# atmega_can.net
KiCad netlist of a schematic drawn in Altium Designer
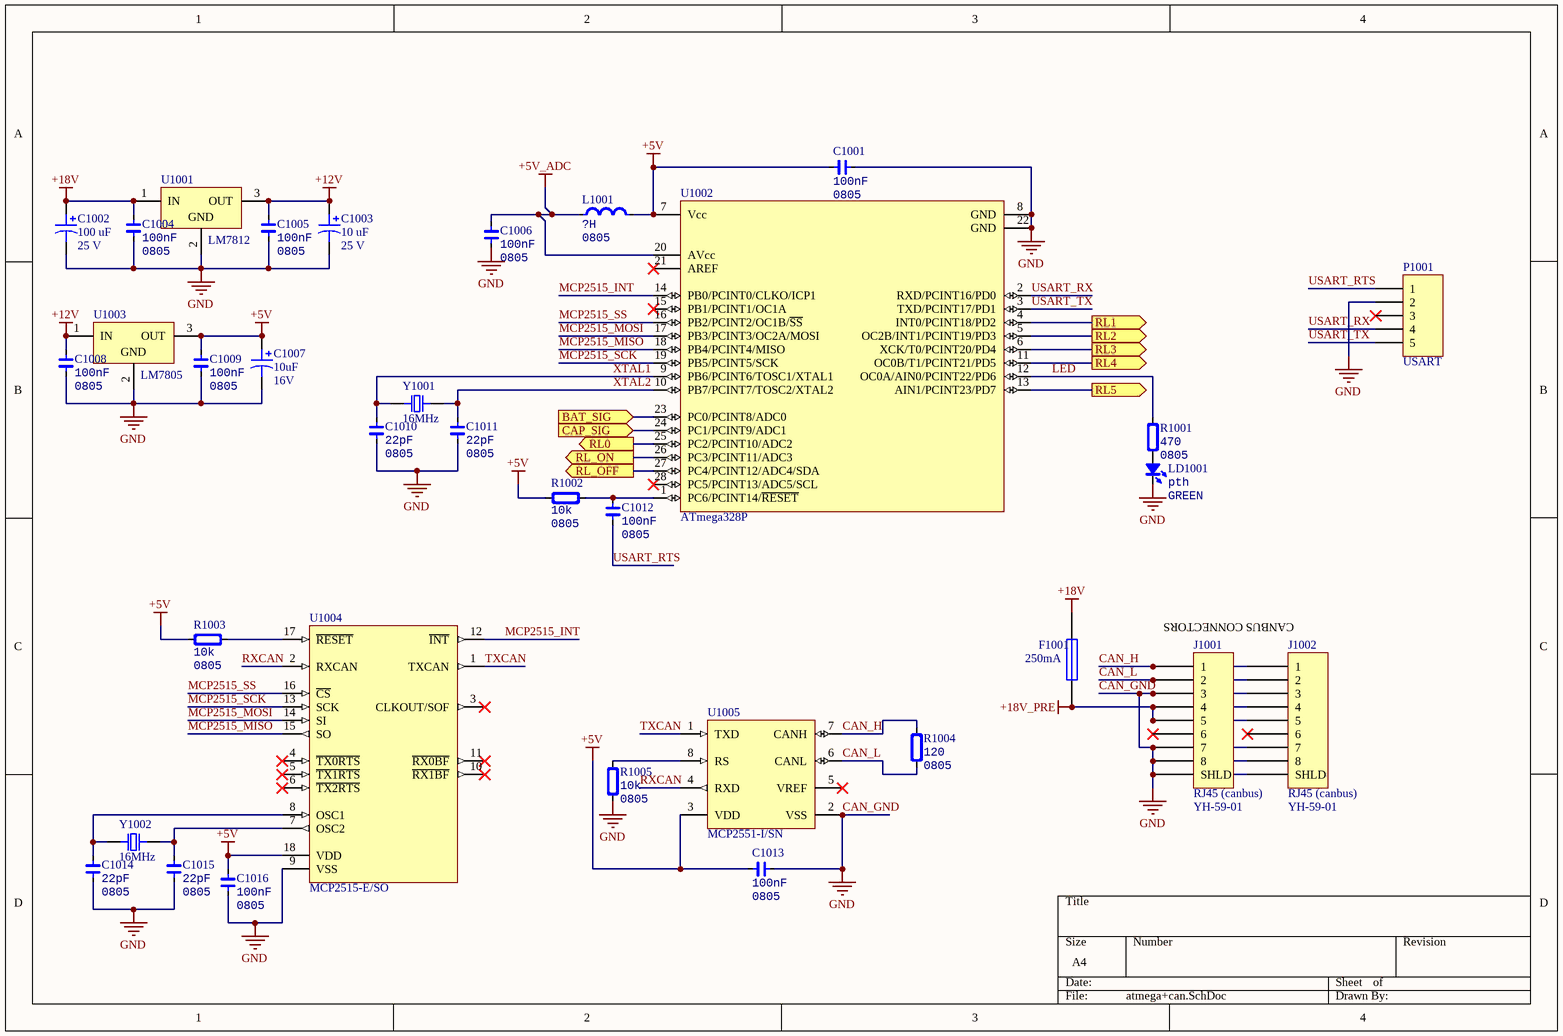
[diagram p0: atmega+can.SchDoc]

(export (version "E")
  (design (tool "Eeschema 10.0.6"))
  (components
    (comp (ref "C1001")
      (value "100nF")
      (footprint "0805C")
      (description "Capacitor")
      (fields (field (name "TYPE") "0805"))
      (libsource (lib "") (part "Cap_0805_1"))
    )
    (comp (ref "C1002")
      (value "100 uF")
      (footprint "CP3.5mm-8.0mm")
      (description "Solid Aluminum Capacitor with Organic Semiconductor Electrolyte: 100uF, 10V, Bulk Pack")
      (fields (field (name "VOLTAGE") "25 V") (field (name "Comment") "CapacitorPol"))
      (libsource (lib "R2R - Nova") (part "CapacitorPol"))
    )
    (comp (ref "C1003")
      (value "10 uF")
      (footprint "CP3.5mm-8.0mm")
      (description "Solid Aluminum Capacitor with Organic Semiconductor Electrolyte: 100uF, 10V, Bulk Pack")
      (fields (field (name "VOLTAGE") "25 V") (field (name "Comment") "CapacitorPol"))
      (libsource (lib "R2R - Nova") (part "CapacitorPol"))
    )
    (comp (ref "C1004")
      (value "100nF")
      (footprint "0805C")
      (description "Capacitor")
      (fields (field (name "TYPE") "0805"))
      (libsource (lib "SCH_Passive") (part "Cap_0805"))
    )
    (comp (ref "C1005")
      (value "100nF")
      (footprint "0805C")
      (description "Capacitor")
      (fields (field (name "TYPE") "0805"))
      (libsource (lib "SCH_Passive") (part "Cap_0805"))
    )
    (comp (ref "C1006")
      (value "100nF")
      (footprint "0805C")
      (description "Capacitor")
      (fields (field (name "TYPE") "0805"))
      (libsource (lib "SCH_Passive") (part "Cap_0805"))
    )
    (comp (ref "C1007")
      (value "10uF")
      (footprint "CP3.5mm-8.0mm")
      (description "Solid Aluminum Capacitor with Organic Semiconductor Electrolyte: 100uF, 10V, Bulk Pack")
      (fields (field (name "VOLTAGE") "16V") (field (name "Comment") "CapacitorPol"))
      (libsource (lib "R2R - Nova") (part "CapacitorPol"))
    )
    (comp (ref "C1008")
      (value "100nF")
      (footprint "0805C")
      (description "Capacitor")
      (fields (field (name "TYPE") "0805"))
      (libsource (lib "SCH_Passive") (part "Cap_0805"))
    )
    (comp (ref "C1009")
      (value "100nF")
      (footprint "0805C")
      (description "Capacitor")
      (fields (field (name "TYPE") "0805"))
      (libsource (lib "SCH_Passive") (part "Cap_0805"))
    )
    (comp (ref "C1010")
      (value "22pF")
      (footprint "0805C")
      (description "Capacitor")
      (fields (field (name "TYPE") "0805"))
      (libsource (lib "SCH_Passive") (part "Cap_0805"))
    )
    (comp (ref "C1011")
      (value "22pF")
      (footprint "0805C")
      (description "Capacitor")
      (fields (field (name "TYPE") "0805"))
      (libsource (lib "SCH_Passive") (part "Cap_0805"))
    )
    (comp (ref "C1012")
      (value "100nF")
      (footprint "0805C")
      (description "Capacitor")
      (fields (field (name "TYPE") "0805"))
      (libsource (lib "") (part "Cap_0805_2"))
    )
    (comp (ref "C1013")
      (value "100nF")
      (footprint "0805C")
      (description "Capacitor")
      (fields (field (name "TYPE") "0805"))
      (libsource (lib "") (part "Cap_0805_1"))
    )
    (comp (ref "C1014")
      (value "22pF")
      (footprint "0805C")
      (description "Capacitor")
      (fields (field (name "TYPE") "0805"))
      (libsource (lib "SCH_Passive") (part "Cap_0805"))
    )
    (comp (ref "C1015")
      (value "22pF")
      (footprint "0805C")
      (description "Capacitor")
      (fields (field (name "TYPE") "0805"))
      (libsource (lib "SCH_Passive") (part "Cap_0805"))
    )
    (comp (ref "C1016")
      (value "100nF")
      (footprint "0805C")
      (description "Capacitor")
      (fields (field (name "TYPE") "0805"))
      (libsource (lib "") (part "Cap_0805_2"))
    )
    (comp (ref "F1001")
      (value "250mA")
      (footprint "Porta Fusivel")
      (description "Fuse")
      (libsource (lib "Miscellaneous Devices") (part "Fuse 1"))
    )
    (comp (ref "J1001")
      (value "RJ45 (canbus)")
      (footprint "ASSMANN A-2004-2-4-LP/FS")
      (description "YH-59-01")
      (fields (field (name "ALTIUM_VALUE") "YH-59-01"))
      (libsource (lib "Connectors") (part "Modular Jack with Shield"))
    )
    (comp (ref "J1002")
      (value "RJ45 (canbus)")
      (footprint "ASSMANN A-2004-2-4-LP/FS")
      (description "YH-59-01")
      (fields (field (name "ALTIUM_VALUE") "YH-59-01"))
      (libsource (lib "Connectors") (part "Modular Jack with Shield"))
    )
    (comp (ref "L1001")
      (value "?H")
      (footprint "0805I")
      (description "Inductor")
      (fields (field (name "TYPE") "0805"))
      (libsource (lib "SCH_Passive") (part "Ind_0805"))
    )
    (comp (ref "LD1001")
      (value "GREEN")
      (footprint "LED3MM")
      (description "LED")
      (fields (field (name "TYPE") "pth"))
      (libsource (lib "SCH_Active") (part "LED_0805"))
    )
    (comp (ref "P1001")
      (value "USART")
      (footprint "HDR1X5")
      (description "Header, 5-Pin")
      (libsource (lib "R2R - Nova") (part "Header 5"))
    )
    (comp (ref "R1001")
      (value "470")
      (footprint "0805C")
      (description "Resistor")
      (fields (field (name "TYPE") "0805"))
      (libsource (lib "SCH_Passive") (part "Res_0805"))
    )
    (comp (ref "R1002")
      (value "10k")
      (footprint "0805C")
      (description "Resistor")
      (fields (field (name "TYPE") "0805"))
      (libsource (lib "SCH_Passive") (part "Res_0805"))
    )
    (comp (ref "R1003")
      (value "10k")
      (footprint "0805C")
      (description "Resistor")
      (fields (field (name "TYPE") "0805"))
      (libsource (lib "SCH_Passive") (part "Res_0805"))
    )
    (comp (ref "R1004")
      (value "120")
      (footprint "0805C")
      (description "Resistor")
      (fields (field (name "TYPE") "0805"))
      (libsource (lib "SCH_Passive") (part "Res_0805"))
    )
    (comp (ref "R1005")
      (value "10k")
      (footprint "0805C")
      (description "Resistor")
      (fields (field (name "TYPE") "0805"))
      (libsource (lib "SCH_Passive") (part "Res_0805"))
    )
    (comp (ref "U1001")
      (value "LM7812")
      (footprint "TO220_deitado")
      (description "Positive-Voltage Regulator")
      (libsource (lib "TI Power Mgt Voltage Regulator") (part "µA7805CKC"))
    )
    (comp (ref "U1002")
      (value "ATmega328P")
      (footprint "DIP28-300(100)")
      (libsource (lib "R2R - Nova") (part "ATmega328P"))
    )
    (comp (ref "U1003")
      (value "LM7805")
      (footprint "TO220_deitado")
      (description "Positive-Voltage Regulator")
      (libsource (lib "TI Power Mgt Voltage Regulator") (part "µA7805CKC"))
    )
    (comp (ref "U1004")
      (value "MCP2515-E/SO")
      (footprint "WSO18_L")
      (description "Stand-Alone CAN Controller With SPI Interface, 18-Pin SOIC, Extended Temperature")
      (libsource (lib "Altium Content Vault") (part "COM-CAN-MCP2515-18"))
    )
    (comp (ref "U1005")
      (value "MCP2551-I/SN")
      (footprint "SOIC08-150(50)")
      (libsource (lib "Altium Content Vault") (part "MCHP-MCP2551-SN8"))
    )
    (comp (ref "Y1001")
      (value "16MHz")
      (footprint "HC49-US-THT")
      (description "Crystal")
      (libsource (lib "R2R - Nova") (part "Crystal"))
    )
    (comp (ref "Y1002")
      (value "16MHz")
      (footprint "HC49-US-THT")
      (description "Crystal")
      (libsource (lib "R2R - Nova") (part "Crystal"))
    )
  )
  (nets
    (net (code "1") (name "+5V") (class "Default")
      (node (ref "C1001") (pin "1") (pinfunction "1_1") (pintype "passive"))
      (node (ref "C1007") (pin "1") (pinfunction "1_1") (pintype "passive"))
      (node (ref "C1009") (pin "2") (pinfunction "2_2") (pintype "passive"))
      (node (ref "C1013") (pin "1") (pinfunction "1_1") (pintype "passive"))
      (node (ref "C1016") (pin "1") (pinfunction "1_1") (pintype "passive"))
      (node (ref "L1001") (pin "2") (pinfunction "2_2") (pintype "passive"))
      (node (ref "R1002") (pin "1") (pinfunction "1_1") (pintype "passive"))
      (node (ref "R1003") (pin "1") (pinfunction "1_1") (pintype "passive"))
      (node (ref "U1002") (pin "7") (pinfunction "Vcc_7") (pintype "passive"))
      (node (ref "U1003") (pin "3") (pinfunction "OUT_3") (pintype "power_in"))
      (node (ref "U1004") (pin "18") (pinfunction "VDD_18") (pintype "power_in"))
      (node (ref "U1005") (pin "3") (pinfunction "VDD_3") (pintype "power_in"))
    )
    (net (code "2") (name "+5V_ADC") (class "Default")
      (node (ref "C1006") (pin "2") (pinfunction "2_2") (pintype "passive"))
      (node (ref "L1001") (pin "1") (pinfunction "1_1") (pintype "passive"))
      (node (ref "U1002") (pin "20") (pinfunction "AVcc_20") (pintype "passive"))
    )
    (net (code "3") (name "+12V") (class "Default")
      (node (ref "C1003") (pin "1") (pinfunction "1_1") (pintype "passive"))
      (node (ref "C1005") (pin "2") (pinfunction "2_2") (pintype "passive"))
      (node (ref "C1008") (pin "2") (pinfunction "2_2") (pintype "passive"))
      (node (ref "U1001") (pin "3") (pinfunction "OUT_3") (pintype "power_in"))
      (node (ref "U1003") (pin "1") (pinfunction "IN_1") (pintype "power_in"))
    )
    (net (code "4") (name "+18V") (class "Default")
      (node (ref "C1002") (pin "1") (pinfunction "1_1") (pintype "passive"))
      (node (ref "C1004") (pin "2") (pinfunction "2_2") (pintype "passive"))
      (node (ref "F1001") (pin "1") (pinfunction "1_1") (pintype "passive"))
      (node (ref "U1001") (pin "1") (pinfunction "IN_1") (pintype "power_in"))
    )
    (net (code "5") (name "+18V_PRE") (class "Default")
      (node (ref "F1001") (pin "2") (pinfunction "2_2") (pintype "passive"))
      (node (ref "J1001") (pin "4") (pinfunction "4_4") (pintype "passive"))
      (node (ref "J1001") (pin "5") (pinfunction "5_5") (pintype "passive"))
      (node (ref "J1002") (pin "4") (pinfunction "4_4") (pintype "passive"))
      (node (ref "J1002") (pin "5") (pinfunction "5_5") (pintype "passive"))
    )
    (net (code "6") (name "/BAT_SIG") (class "Default")
      (node (ref "U1002") (pin "23") (pinfunction "PC0/PCINT8/ADC0_23") (pintype "bidirectional"))
    )
    (net (code "7") (name "/CAN_H") (class "Default")
      (node (ref "J1001") (pin "1") (pinfunction "1_1") (pintype "passive"))
      (node (ref "J1002") (pin "1") (pinfunction "1_1") (pintype "passive"))
      (node (ref "R1004") (pin "2") (pinfunction "2_2") (pintype "passive"))
      (node (ref "U1005") (pin "7") (pinfunction "CANH_7") (pintype "bidirectional"))
    )
    (net (code "8") (name "/CAN_L") (class "Default")
      (node (ref "J1001") (pin "2") (pinfunction "2_2") (pintype "passive"))
      (node (ref "J1002") (pin "2") (pinfunction "2_2") (pintype "passive"))
      (node (ref "R1004") (pin "1") (pinfunction "1_1") (pintype "passive"))
      (node (ref "U1005") (pin "6") (pinfunction "CANL_6") (pintype "bidirectional"))
    )
    (net (code "9") (name "/CAP_SIG") (class "Default")
      (node (ref "U1002") (pin "24") (pinfunction "PC1/PCINT9/ADC1_24") (pintype "bidirectional"))
    )
    (net (code "10") (name "/LED") (class "Default")
      (node (ref "R1001") (pin "2") (pinfunction "2_2") (pintype "passive"))
      (node (ref "U1002") (pin "12") (pinfunction "OC0A/AIN0/PCINT22/PD6_12") (pintype "bidirectional"))
    )
    (net (code "11") (name "/MCP2515_INT") (class "Default")
      (node (ref "U1002") (pin "14") (pinfunction "PB0/PCINT0/CLKO/ICP1_14") (pintype "bidirectional"))
      (node (ref "U1004") (pin "12") (pinfunction "~{INT}_12") (pintype "output"))
    )
    (net (code "12") (name "/MCP2515_MISO") (class "Default")
      (node (ref "U1002") (pin "18") (pinfunction "PB4/PCINT4/MISO_18") (pintype "bidirectional"))
      (node (ref "U1004") (pin "15") (pinfunction "SO_15") (pintype "output"))
    )
    (net (code "13") (name "/MCP2515_MOSI") (class "Default")
      (node (ref "U1002") (pin "17") (pinfunction "PB3/PCINT3/OC2A/MOSI_17") (pintype "bidirectional"))
      (node (ref "U1004") (pin "14") (pinfunction "SI_14") (pintype "input"))
    )
    (net (code "14") (name "/MCP2515_SCK") (class "Default")
      (node (ref "U1002") (pin "19") (pinfunction "PB5/PCINT5/SCK_19") (pintype "bidirectional"))
      (node (ref "U1004") (pin "13") (pinfunction "SCK_13") (pintype "input"))
    )
    (net (code "15") (name "/MCP2515_SS") (class "Default")
      (node (ref "U1002") (pin "16") (pinfunction "PB2/PCINT2/OC1B/~{SS}_16") (pintype "bidirectional"))
      (node (ref "U1004") (pin "16") (pinfunction "~{CS}_16") (pintype "input"))
    )
    (net (code "16") (name "/RL0") (class "Default")
      (node (ref "U1002") (pin "25") (pinfunction "PC2/PCINT10/ADC2_25") (pintype "bidirectional"))
    )
    (net (code "17") (name "/RL1") (class "Default")
      (node (ref "U1002") (pin "4") (pinfunction "INT0/PCINT18/PD2_4") (pintype "bidirectional"))
    )
    (net (code "18") (name "/RL2") (class "Default")
      (node (ref "U1002") (pin "5") (pinfunction "OC2B/INT1/PCINT19/PD3_5") (pintype "bidirectional"))
    )
    (net (code "19") (name "/RL3") (class "Default")
      (node (ref "U1002") (pin "6") (pinfunction "XCK/T0/PCINT20/PD4_6") (pintype "bidirectional"))
    )
    (net (code "20") (name "/RL4") (class "Default")
      (node (ref "U1002") (pin "11") (pinfunction "OC0B/T1/PCINT21/PD5_11") (pintype "bidirectional"))
    )
    (net (code "21") (name "/RL5") (class "Default")
      (node (ref "U1002") (pin "13") (pinfunction "AIN1/PCINT23/PD7_13") (pintype "bidirectional"))
    )
    (net (code "22") (name "/RL_OFF") (class "Default")
      (node (ref "U1002") (pin "27") (pinfunction "PC4/PCINT12/ADC4/SDA_27") (pintype "bidirectional"))
    )
    (net (code "23") (name "/RL_ON") (class "Default")
      (node (ref "U1002") (pin "26") (pinfunction "PC3/PCINT11/ADC3_26") (pintype "bidirectional"))
    )
    (net (code "24") (name "/RXCAN") (class "Default")
      (node (ref "U1004") (pin "2") (pinfunction "RXCAN_2") (pintype "input"))
      (node (ref "U1005") (pin "4") (pinfunction "RXD_4") (pintype "output"))
    )
    (net (code "25") (name "/TXCAN") (class "Default")
      (node (ref "U1004") (pin "1") (pinfunction "TXCAN_1") (pintype "output"))
      (node (ref "U1005") (pin "1") (pinfunction "TXD_1") (pintype "input"))
    )
    (net (code "26") (name "/USART_RTS") (class "Default")
      (node (ref "C1012") (pin "2") (pinfunction "2_2") (pintype "passive"))
      (node (ref "P1001") (pin "1") (pinfunction "1_1") (pintype "passive"))
    )
    (net (code "27") (name "/USART_RX") (class "Default")
      (node (ref "P1001") (pin "4") (pinfunction "4_4") (pintype "passive"))
      (node (ref "U1002") (pin "2") (pinfunction "RXD/PCINT16/PD0_2") (pintype "bidirectional"))
    )
    (net (code "28") (name "/USART_TX") (class "Default")
      (node (ref "P1001") (pin "5") (pinfunction "5_5") (pintype "passive"))
      (node (ref "U1002") (pin "3") (pinfunction "TXD/PCINT17/PD1_3") (pintype "bidirectional"))
    )
    (net (code "29") (name "/XTAL1") (class "Default")
      (node (ref "C1010") (pin "2") (pinfunction "2_2") (pintype "passive"))
      (node (ref "U1002") (pin "9") (pinfunction "PB6/PCINT6/TOSC1/XTAL1_9") (pintype "bidirectional"))
      (node (ref "Y1001") (pin "1") (pinfunction "1_1") (pintype "passive"))
    )
    (net (code "30") (name "/XTAL2") (class "Default")
      (node (ref "C1011") (pin "2") (pinfunction "2_2") (pintype "passive"))
      (node (ref "U1002") (pin "10") (pinfunction "PB7/PCINT7/TOSC2/XTAL2_10") (pintype "bidirectional"))
      (node (ref "Y1001") (pin "2") (pinfunction "2_2") (pintype "passive"))
    )
    (net (code "31") (name "GND") (class "Default")
      (node (ref "C1001") (pin "2") (pinfunction "2_2") (pintype "passive"))
      (node (ref "C1002") (pin "2") (pinfunction "2_2") (pintype "passive"))
      (node (ref "C1003") (pin "2") (pinfunction "2_2") (pintype "passive"))
      (node (ref "C1004") (pin "1") (pinfunction "1_1") (pintype "passive"))
      (node (ref "C1005") (pin "1") (pinfunction "1_1") (pintype "passive"))
      (node (ref "C1006") (pin "1") (pinfunction "1_1") (pintype "passive"))
      (node (ref "C1007") (pin "2") (pinfunction "2_2") (pintype "passive"))
      (node (ref "C1008") (pin "1") (pinfunction "1_1") (pintype "passive"))
      (node (ref "C1009") (pin "1") (pinfunction "1_1") (pintype "passive"))
      (node (ref "C1010") (pin "1") (pinfunction "1_1") (pintype "passive"))
      (node (ref "C1011") (pin "1") (pinfunction "1_1") (pintype "passive"))
      (node (ref "C1013") (pin "2") (pinfunction "2_2") (pintype "passive"))
      (node (ref "C1014") (pin "1") (pinfunction "1_1") (pintype "passive"))
      (node (ref "C1015") (pin "1") (pinfunction "1_1") (pintype "passive"))
      (node (ref "C1016") (pin "2") (pinfunction "2_2") (pintype "passive"))
      (node (ref "J1001") (pin "3") (pinfunction "3_3") (pintype "passive"))
      (node (ref "J1001") (pin "7") (pinfunction "7_7") (pintype "passive"))
      (node (ref "J1001") (pin "8") (pinfunction "8_8") (pintype "passive"))
      (node (ref "J1001") (pin "S") (pinfunction "SHLD_S") (pintype "passive"))
      (node (ref "J1002") (pin "3") (pinfunction "3_3") (pintype "passive"))
      (node (ref "J1002") (pin "7") (pinfunction "7_7") (pintype "passive"))
      (node (ref "J1002") (pin "8") (pinfunction "8_8") (pintype "passive"))
      (node (ref "J1002") (pin "S") (pinfunction "SHLD_S") (pintype "passive"))
      (node (ref "LD1001") (pin "2") (pinfunction "K_2") (pintype "passive"))
      (node (ref "P1001") (pin "2") (pinfunction "2_2") (pintype "passive"))
      (node (ref "R1005") (pin "2") (pinfunction "2_2") (pintype "passive"))
      (node (ref "U1001") (pin "2") (pinfunction "GND_2") (pintype "power_in"))
      (node (ref "U1002") (pin "22") (pinfunction "GND_22") (pintype "passive"))
      (node (ref "U1002") (pin "8") (pinfunction "GND_8") (pintype "passive"))
      (node (ref "U1003") (pin "2") (pinfunction "GND_2") (pintype "power_in"))
      (node (ref "U1004") (pin "9") (pinfunction "VSS_9") (pintype "power_in"))
      (node (ref "U1005") (pin "2") (pinfunction "VSS_2") (pintype "power_in"))
    )
    (net (code "32") (name "Net-(LD1001-A)") (class "Default")
      (node (ref "LD1001") (pin "1") (pinfunction "A_1") (pintype "passive"))
      (node (ref "R1001") (pin "1") (pinfunction "1_1") (pintype "passive"))
    )
    (net (code "33") (name "Net-(U1002-PC6{slash}PCINT14{slash}~{RESET})") (class "Default")
      (node (ref "C1012") (pin "1") (pinfunction "1_1") (pintype "passive"))
      (node (ref "R1002") (pin "2") (pinfunction "2_2") (pintype "passive"))
      (node (ref "U1002") (pin "1") (pinfunction "PC6/PCINT14/~{RESET}_1") (pintype "bidirectional"))
    )
    (net (code "34") (name "Net-(U1004-OSC1)") (class "Default")
      (node (ref "C1014") (pin "2") (pinfunction "2_2") (pintype "passive"))
      (node (ref "U1004") (pin "8") (pinfunction "OSC1_8") (pintype "input"))
      (node (ref "Y1002") (pin "1") (pinfunction "1_1") (pintype "passive"))
    )
    (net (code "35") (name "Net-(U1004-OSC2)") (class "Default")
      (node (ref "C1015") (pin "2") (pinfunction "2_2") (pintype "passive"))
      (node (ref "U1004") (pin "7") (pinfunction "OSC2_7") (pintype "output"))
      (node (ref "Y1002") (pin "2") (pinfunction "2_2") (pintype "passive"))
    )
    (net (code "36") (name "Net-(U1004-~{RESET})") (class "Default")
      (node (ref "R1003") (pin "2") (pinfunction "2_2") (pintype "passive"))
      (node (ref "U1004") (pin "17") (pinfunction "~{RESET}_17") (pintype "input"))
    )
    (net (code "37") (name "Net-(U1005-RS)") (class "Default")
      (node (ref "R1005") (pin "1") (pinfunction "1_1") (pintype "passive"))
      (node (ref "U1005") (pin "8") (pinfunction "RS_8") (pintype "input"))
    )
    (net (code "38") (name "unconnected-(J1001-Pad6)") (class "Default")
      (node (ref "J1001") (pin "6") (pinfunction "6_6") (pintype "passive+no_connect"))
    )
    (net (code "39") (name "unconnected-(J1002-Pad6)") (class "Default")
      (node (ref "J1002") (pin "6") (pinfunction "6_6") (pintype "passive+no_connect"))
    )
    (net (code "40") (name "unconnected-(P1001-Pad3)") (class "Default")
      (node (ref "P1001") (pin "3") (pinfunction "3_3") (pintype "passive+no_connect"))
    )
    (net (code "41") (name "unconnected-(U1002-AREF-Pad21)") (class "Default")
      (node (ref "U1002") (pin "21") (pinfunction "AREF_21") (pintype "passive+no_connect"))
    )
    (net (code "42") (name "unconnected-(U1002-PB1{slash}PCINT1{slash}OC1A-Pad15)") (class "Default")
      (node (ref "U1002") (pin "15") (pinfunction "PB1/PCINT1/OC1A_15") (pintype "bidirectional+no_connect"))
    )
    (net (code "43") (name "unconnected-(U1002-PC5{slash}PCINT13{slash}ADC5{slash}SCL-Pad28)") (class "Default")
      (node (ref "U1002") (pin "28") (pinfunction "PC5/PCINT13/ADC5/SCL_28") (pintype "bidirectional+no_connect"))
    )
    (net (code "44") (name "unconnected-(U1004-CLKOUT{slash}SOF-Pad3)") (class "Default")
      (node (ref "U1004") (pin "3") (pinfunction "CLKOUT/SOF_3") (pintype "output+no_connect"))
    )
    (net (code "45") (name "unconnected-(U1004-~{RX0BF}-Pad11)") (class "Default")
      (node (ref "U1004") (pin "11") (pinfunction "~{RX0BF}_11") (pintype "output+no_connect"))
    )
    (net (code "46") (name "unconnected-(U1004-~{RX1BF}-Pad10)") (class "Default")
      (node (ref "U1004") (pin "10") (pinfunction "~{RX1BF}_10") (pintype "output+no_connect"))
    )
    (net (code "47") (name "unconnected-(U1004-~{TX0RTS}-Pad4)") (class "Default")
      (node (ref "U1004") (pin "4") (pinfunction "~{TX0RTS}_4") (pintype "input+no_connect"))
    )
    (net (code "48") (name "unconnected-(U1004-~{TX1RTS}-Pad5)") (class "Default")
      (node (ref "U1004") (pin "5") (pinfunction "~{TX1RTS}_5") (pintype "input+no_connect"))
    )
    (net (code "49") (name "unconnected-(U1004-~{TX2RTS}-Pad6)") (class "Default")
      (node (ref "U1004") (pin "6") (pinfunction "~{TX2RTS}_6") (pintype "input+no_connect"))
    )
    (net (code "50") (name "unconnected-(U1005-VREF-Pad5)") (class "Default")
      (node (ref "U1005") (pin "5") (pinfunction "VREF_5") (pintype "power_in+no_connect"))
    )
  )
)
